# EDA.net
KiCad netlist of a schematic drawn in EasyEDA
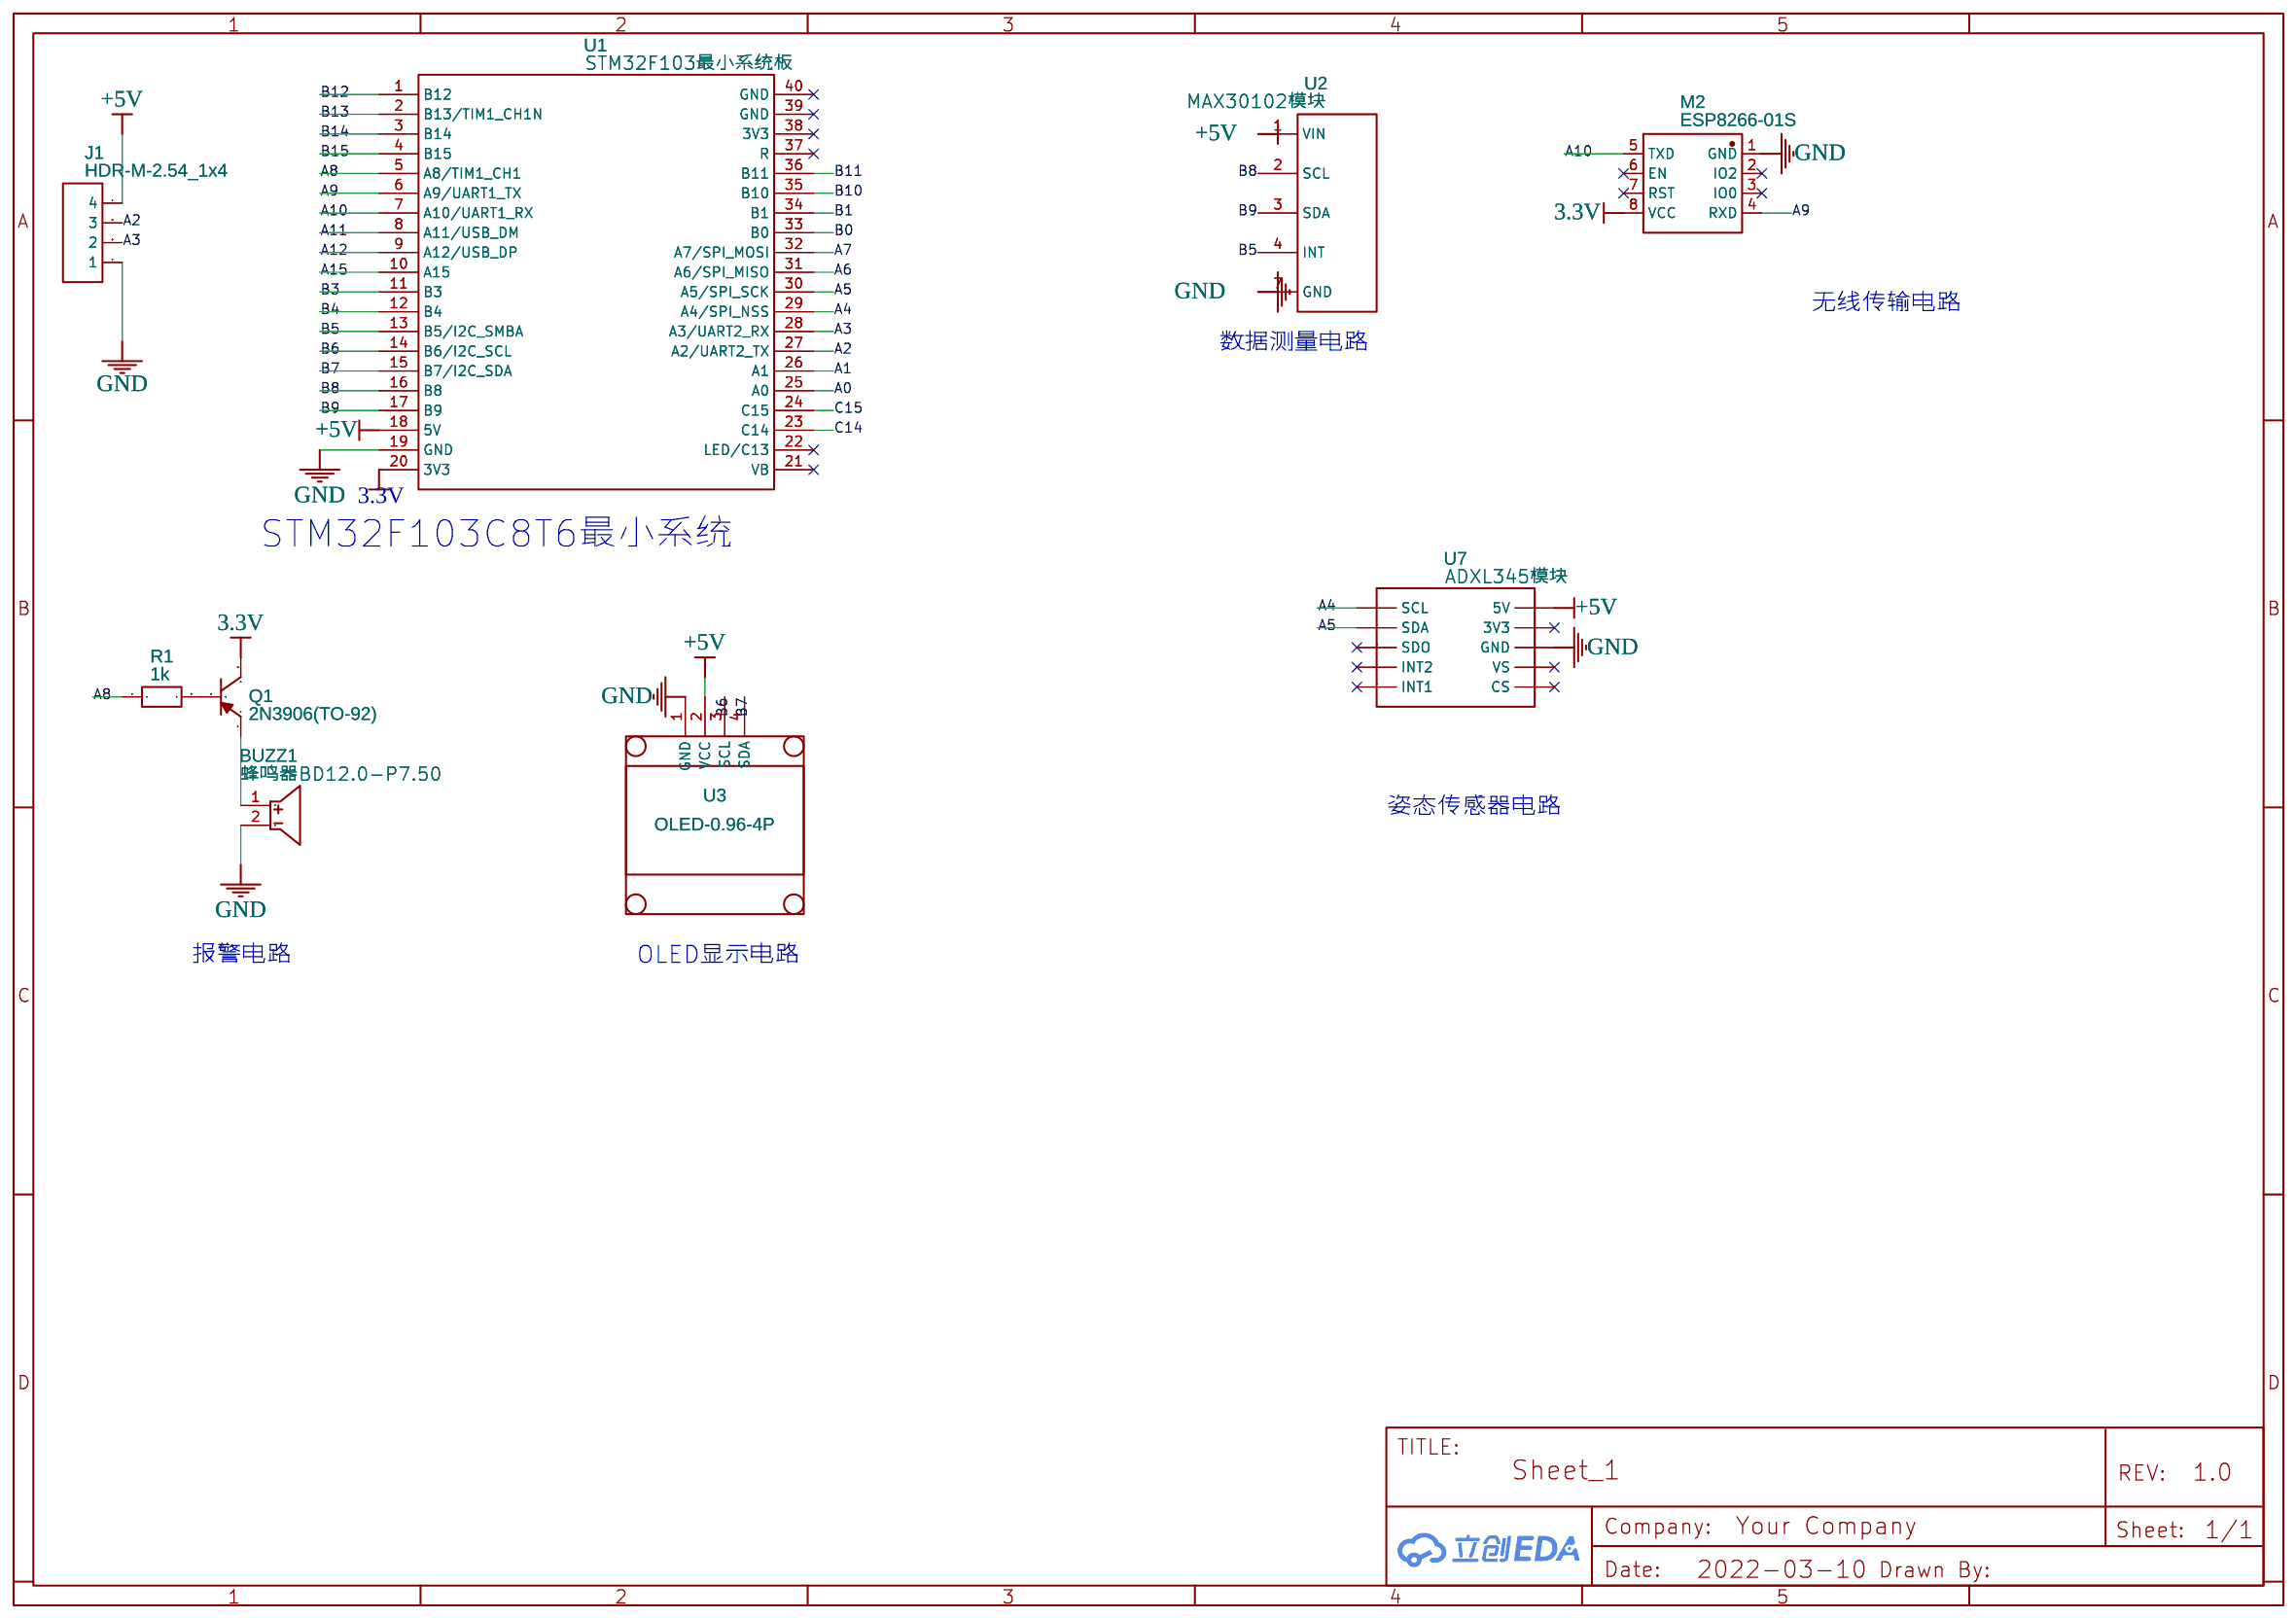
[diagram p0: schematic sheet]

(export (version "E")
  (design (tool "Eeschema 10.0.6"))
  (components
    (comp (ref "BUZZ1")
      (value "蜂鸣器BD12.0-P7.50")
      (fields (field (name "BOM_Supplier Part") "C9900003117"))
      (libsource (lib "") (part "蜂鸣器BD12.0-P7.50"))
    )
    (comp (ref "J1")
      (value "HDR-M-2.54_1x4")
      (fields (field (name "BOM_Supplier Part") "C124378"))
      (libsource (lib "") (part "HDR-M-2.54_1x4"))
    )
    (comp (ref "M2") (value "ESP8266-01S") (libsource (lib "") (part "ESP8266-01S")))
    (comp (ref "Q1")
      (value "2N3906(TO-92)")
      (fields (field (name "BOM_Manufacturer Part") "2N3906") (field (name "BOM_Supplier Part") "C9809"))
      (libsource (lib "") (part "2N3906(TO-92)"))
    )
    (comp (ref "R1") (value "1k") (libsource (lib "") (part "R_AXIAL-0.3_EU")))
    (comp (ref "U1") (value "STM32F103最小系统板") (libsource (lib "") (part "STM32F103最小系统板")))
    (comp (ref "U2") (value "MAX30102模块") (libsource (lib "") (part "MAX30102模块")))
    (comp (ref "U3")
      (value "OLED-0.96-4P")
      (fields
        (field (name "BOM_Manufacturer Part") "oled-0.96-4p-spi")
        (field (name "BOM_Supplier Part") "undefined")
      )
      (libsource (lib "") (part "OLED-0.96-4P"))
    )
    (comp (ref "U7") (value "ADXL345模块") (libsource (lib "") (part "ADXL345模块")))
  )
  (nets
    (net (code "1") (name "+5V") (class "Default")
      (node (ref "J1") (pin "4") (pinfunction "4_4") (pintype "unspecified"))
      (node (ref "U1") (pin "18") (pinfunction "5V_18") (pintype "unspecified"))
      (node (ref "U2") (pin "1") (pinfunction "VIN_1") (pintype "unspecified"))
      (node (ref "U3") (pin "2") (pinfunction "VCC_2") (pintype "unspecified"))
      (node (ref "U7") (pin "10") (pinfunction "5V_10") (pintype "unspecified"))
    )
    (net (code "2") (name "/A0") (class "Default")
      (node (ref "U1") (pin "25") (pinfunction "A0_25") (pintype "unspecified"))
    )
    (net (code "3") (name "/A1") (class "Default")
      (node (ref "U1") (pin "26") (pinfunction "A1_26") (pintype "unspecified"))
    )
    (net (code "4") (name "/A2") (class "Default")
      (node (ref "J1") (pin "3") (pinfunction "3_3") (pintype "unspecified"))
      (node (ref "U1") (pin "27") (pinfunction "A2/UART2_TX_27") (pintype "unspecified"))
    )
    (net (code "5") (name "/A3") (class "Default")
      (node (ref "J1") (pin "2") (pinfunction "2_2") (pintype "unspecified"))
      (node (ref "U1") (pin "28") (pinfunction "A3/UART2_RX_28") (pintype "unspecified"))
    )
    (net (code "6") (name "/A4") (class "Default")
      (node (ref "U1") (pin "29") (pinfunction "A4/SPI_NSS_29") (pintype "unspecified"))
      (node (ref "U7") (pin "1") (pinfunction "SCL_1") (pintype "unspecified"))
    )
    (net (code "7") (name "/A5") (class "Default")
      (node (ref "U1") (pin "30") (pinfunction "A5/SPI_SCK_30") (pintype "unspecified"))
      (node (ref "U7") (pin "2") (pinfunction "SDA_2") (pintype "unspecified"))
    )
    (net (code "8") (name "/A6") (class "Default")
      (node (ref "U1") (pin "31") (pinfunction "A6/SPI_MISO_31") (pintype "unspecified"))
    )
    (net (code "9") (name "/A7") (class "Default")
      (node (ref "U1") (pin "32") (pinfunction "A7/SPI_MOSI_32") (pintype "unspecified"))
    )
    (net (code "10") (name "/A8") (class "Default")
      (node (ref "R1") (pin "1") (pinfunction "1_1") (pintype "unspecified"))
      (node (ref "U1") (pin "5") (pinfunction "A8/TIM1_CH1_5") (pintype "unspecified"))
    )
    (net (code "11") (name "/A9") (class "Default")
      (node (ref "M2") (pin "4") (pinfunction "RXD_4") (pintype "unspecified"))
      (node (ref "U1") (pin "6") (pinfunction "A9/UART1_TX_6") (pintype "unspecified"))
    )
    (net (code "12") (name "/A10") (class "Default")
      (node (ref "M2") (pin "5") (pinfunction "TXD_5") (pintype "unspecified"))
      (node (ref "U1") (pin "7") (pinfunction "A10/UART1_RX_7") (pintype "unspecified"))
    )
    (net (code "13") (name "/A11") (class "Default")
      (node (ref "U1") (pin "8") (pinfunction "A11/USB_DM_8") (pintype "unspecified"))
    )
    (net (code "14") (name "/A12") (class "Default")
      (node (ref "U1") (pin "9") (pinfunction "A12/USB_DP_9") (pintype "unspecified"))
    )
    (net (code "15") (name "/A15") (class "Default")
      (node (ref "U1") (pin "10") (pinfunction "A15_10") (pintype "unspecified"))
    )
    (net (code "16") (name "/B0") (class "Default")
      (node (ref "U1") (pin "33") (pinfunction "B0_33") (pintype "unspecified"))
    )
    (net (code "17") (name "/B1") (class "Default")
      (node (ref "U1") (pin "34") (pinfunction "B1_34") (pintype "unspecified"))
    )
    (net (code "18") (name "/B3") (class "Default")
      (node (ref "U1") (pin "11") (pinfunction "B3_11") (pintype "unspecified"))
    )
    (net (code "19") (name "/B4") (class "Default")
      (node (ref "U1") (pin "12") (pinfunction "B4_12") (pintype "unspecified"))
    )
    (net (code "20") (name "/B5") (class "Default")
      (node (ref "U1") (pin "13") (pinfunction "B5/I2C_SMBA_13") (pintype "unspecified"))
      (node (ref "U2") (pin "4") (pinfunction "INT_4") (pintype "unspecified"))
    )
    (net (code "21") (name "/B6") (class "Default")
      (node (ref "U1") (pin "14") (pinfunction "B6/I2C_SCL_14") (pintype "unspecified"))
      (node (ref "U3") (pin "3") (pinfunction "SCL_3") (pintype "unspecified"))
    )
    (net (code "22") (name "/B7") (class "Default")
      (node (ref "U1") (pin "15") (pinfunction "B7/I2C_SDA_15") (pintype "unspecified"))
      (node (ref "U3") (pin "4") (pinfunction "SDA_4") (pintype "unspecified"))
    )
    (net (code "23") (name "/B8") (class "Default")
      (node (ref "U1") (pin "16") (pinfunction "B8_16") (pintype "unspecified"))
      (node (ref "U2") (pin "2") (pinfunction "SCL_2") (pintype "unspecified"))
    )
    (net (code "24") (name "/B9") (class "Default")
      (node (ref "U1") (pin "17") (pinfunction "B9_17") (pintype "unspecified"))
      (node (ref "U2") (pin "3") (pinfunction "SDA_3") (pintype "unspecified"))
    )
    (net (code "25") (name "/B10") (class "Default")
      (node (ref "U1") (pin "35") (pinfunction "B10_35") (pintype "unspecified"))
    )
    (net (code "26") (name "/B11") (class "Default")
      (node (ref "U1") (pin "36") (pinfunction "B11_36") (pintype "unspecified"))
    )
    (net (code "27") (name "/B12") (class "Default")
      (node (ref "U1") (pin "1") (pinfunction "B12_1") (pintype "unspecified"))
    )
    (net (code "28") (name "/B13") (class "Default")
      (node (ref "U1") (pin "2") (pinfunction "B13/TIM1_CH1N_2") (pintype "unspecified"))
    )
    (net (code "29") (name "/B14") (class "Default")
      (node (ref "U1") (pin "3") (pinfunction "B14_3") (pintype "unspecified"))
    )
    (net (code "30") (name "/B15") (class "Default")
      (node (ref "U1") (pin "4") (pinfunction "B15_4") (pintype "unspecified"))
    )
    (net (code "31") (name "/C14") (class "Default")
      (node (ref "U1") (pin "23") (pinfunction "C14_23") (pintype "unspecified"))
    )
    (net (code "32") (name "/C15") (class "Default")
      (node (ref "U1") (pin "24") (pinfunction "C15_24") (pintype "unspecified"))
    )
    (net (code "33") (name "3.3V") (class "Default")
      (node (ref "M2") (pin "8") (pinfunction "VCC_8") (pintype "unspecified"))
      (node (ref "Q1") (pin "3") (pinfunction "C_3") (pintype "input"))
      (node (ref "U1") (pin "20") (pinfunction "3V3_20") (pintype "unspecified"))
    )
    (net (code "34") (name "GND") (class "Default")
      (node (ref "BUZZ1") (pin "2") (pinfunction "2_2") (pintype "unspecified"))
      (node (ref "J1") (pin "1") (pinfunction "1_1") (pintype "unspecified"))
      (node (ref "M2") (pin "1") (pinfunction "GND_1") (pintype "unspecified"))
      (node (ref "U1") (pin "19") (pinfunction "GND_19") (pintype "unspecified"))
      (node (ref "U2") (pin "7") (pinfunction "GND_7") (pintype "unspecified"))
      (node (ref "U3") (pin "1") (pinfunction "GND_1") (pintype "unspecified"))
      (node (ref "U7") (pin "8") (pinfunction "GND_8") (pintype "unspecified"))
    )
    (net (code "35") (name "Net-(Q1-B)") (class "Default")
      (node (ref "Q1") (pin "2") (pinfunction "B_2") (pintype "input"))
      (node (ref "R1") (pin "2") (pinfunction "2_2") (pintype "unspecified"))
    )
    (net (code "36") (name "Net-(Q1-E)") (class "Default")
      (node (ref "BUZZ1") (pin "1") (pinfunction "1_1") (pintype "unspecified"))
      (node (ref "Q1") (pin "1") (pinfunction "E_1") (pintype "input"))
    )
    (net (code "37") (name "unconnected-(M2-EN-Pad6)") (class "Default")
      (node (ref "M2") (pin "6") (pinfunction "EN_6") (pintype "unspecified+no_connect"))
    )
    (net (code "38") (name "unconnected-(M2-IO0-Pad3)") (class "Default")
      (node (ref "M2") (pin "3") (pinfunction "IO0_3") (pintype "unspecified+no_connect"))
    )
    (net (code "39") (name "unconnected-(M2-IO2-Pad2)") (class "Default")
      (node (ref "M2") (pin "2") (pinfunction "IO2_2") (pintype "unspecified+no_connect"))
    )
    (net (code "40") (name "unconnected-(M2-RST-Pad7)") (class "Default")
      (node (ref "M2") (pin "7") (pinfunction "RST_7") (pintype "unspecified+no_connect"))
    )
    (net (code "41") (name "unconnected-(U1-3V3-Pad38)") (class "Default")
      (node (ref "U1") (pin "38") (pinfunction "3V3_38") (pintype "unspecified+no_connect"))
    )
    (net (code "42") (name "unconnected-(U1-GND-Pad39)") (class "Default")
      (node (ref "U1") (pin "39") (pinfunction "GND_39") (pintype "unspecified+no_connect"))
    )
    (net (code "43") (name "unconnected-(U1-GND-Pad40)") (class "Default")
      (node (ref "U1") (pin "40") (pinfunction "GND_40") (pintype "unspecified+no_connect"))
    )
    (net (code "44") (name "unconnected-(U1-LED{slash}C13-Pad22)") (class "Default")
      (node (ref "U1") (pin "22") (pinfunction "LED/C13_22") (pintype "unspecified+no_connect"))
    )
    (net (code "45") (name "unconnected-(U1-R-Pad37)") (class "Default")
      (node (ref "U1") (pin "37") (pinfunction "R_37") (pintype "unspecified+no_connect"))
    )
    (net (code "46") (name "unconnected-(U1-VB-Pad21)") (class "Default")
      (node (ref "U1") (pin "21") (pinfunction "VB_21") (pintype "unspecified+no_connect"))
    )
    (net (code "47") (name "unconnected-(U7-3V3-Pad9)") (class "Default")
      (node (ref "U7") (pin "9") (pinfunction "3V3_9") (pintype "unspecified+no_connect"))
    )
    (net (code "48") (name "unconnected-(U7-CS-Pad6)") (class "Default")
      (node (ref "U7") (pin "6") (pinfunction "CS_6") (pintype "unspecified+no_connect"))
    )
    (net (code "49") (name "unconnected-(U7-INT1-Pad5)") (class "Default")
      (node (ref "U7") (pin "5") (pinfunction "INT1_5") (pintype "unspecified+no_connect"))
    )
    (net (code "50") (name "unconnected-(U7-INT2-Pad4)") (class "Default")
      (node (ref "U7") (pin "4") (pinfunction "INT2_4") (pintype "unspecified+no_connect"))
    )
    (net (code "51") (name "unconnected-(U7-SDO-Pad3)") (class "Default")
      (node (ref "U7") (pin "3") (pinfunction "SDO_3") (pintype "unspecified+no_connect"))
    )
    (net (code "52") (name "unconnected-(U7-VS-Pad7)") (class "Default")
      (node (ref "U7") (pin "7") (pinfunction "VS_7") (pintype "unspecified+no_connect"))
    )
  )
)
